# dimmerac_supervisorio_REV3.net
KiCad netlist of a schematic drawn in EAGLE
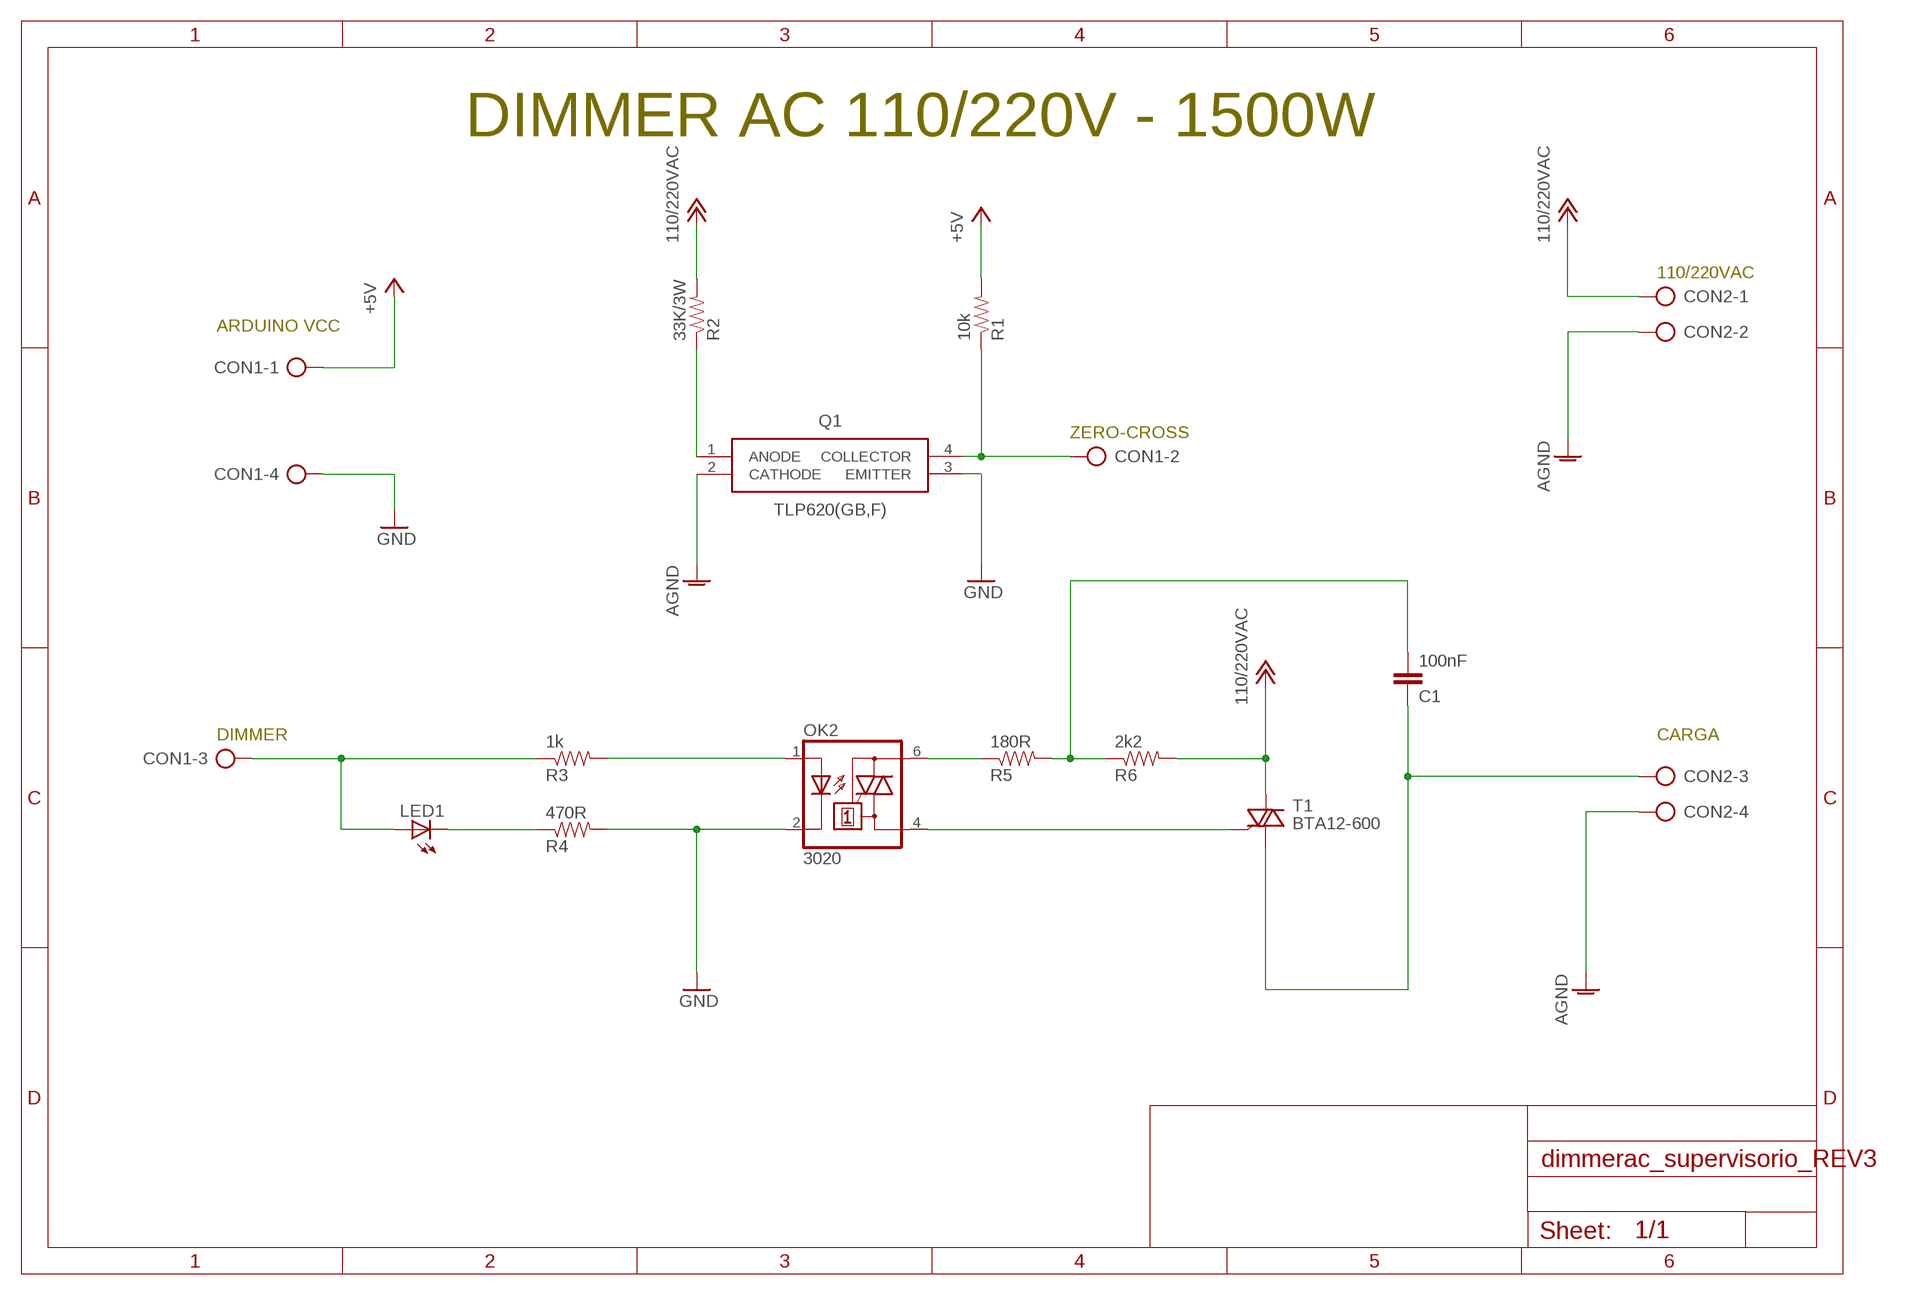
[diagram p0: schematic, sheet 1]

(export (version "E")
  (design (tool "Eeschema 10.0.6"))
  (components
    (comp (ref "C1")
      (value "100nF")
      (footprint "eagle-import:C15B7")
      (libsource (lib "eagle-import") (part "CAP_600V"))
    )
    (comp (ref "CON1")
      (value "AK500/4")
      (footprint "eagle-import:AK500_4")
      (libsource (lib "eagle-import") (part "AK500/4"))
    )
    (comp (ref "CON2")
      (value "AK500/4")
      (footprint "eagle-import:AK500_4")
      (libsource (lib "eagle-import") (part "AK500/4"))
    )
    (comp (ref "LED1")
      (value "LED5MM")
      (footprint "eagle-import:LED5MM")
      (libsource (lib "eagle-import") (part "LED5MM"))
    )
    (comp (ref "OK2")
      (value "3020")
      (footprint "eagle-import:DIL06")
      (fields (field (name "MF") "FAIRCHILD SEMICONDUCTOR") (field (name "MPN") "MOC3020-M"))
      (libsource (lib "eagle-import") (part "MOC30M20"))
    )
    (comp (ref "Q1")
      (value "TLP620(GB,F)")
      (footprint "eagle-import:DIP762W60P254L448H380Q4N")
      (fields (field (name "RS_PART_NUMBER") "0186189"))
      (libsource (lib "eagle-import") (part "TLP620(GB,F)"))
    )
    (comp (ref "R1")
      (value "10k")
      (footprint "eagle-import:AXIAL-0.3")
      (libsource (lib "eagle-import") (part "RESISTORAXIAL-0.3"))
    )
    (comp (ref "R2")
      (value "33K/3W")
      (footprint "eagle-import:AXIAL-0.6")
      (libsource (lib "eagle-import") (part "RES_5W"))
    )
    (comp (ref "R3")
      (value "1k")
      (footprint "eagle-import:AXIAL-0.3")
      (libsource (lib "eagle-import") (part "RESISTORAXIAL-0.3"))
    )
    (comp (ref "R4")
      (value "470R")
      (footprint "eagle-import:AXIAL-0.3")
      (libsource (lib "eagle-import") (part "RESISTORAXIAL-0.3"))
    )
    (comp (ref "R5")
      (value "180R")
      (footprint "eagle-import:AXIAL-0.3")
      (libsource (lib "eagle-import") (part "RESISTORAXIAL-0.3"))
    )
    (comp (ref "R6")
      (value "2k2")
      (footprint "eagle-import:AXIAL-0.3")
      (libsource (lib "eagle-import") (part "RESISTORAXIAL-0.3"))
    )
    (comp (ref "T1")
      (value "BTA12-600")
      (footprint "eagle-import:TO220BH")
      (libsource (lib "eagle-import") (part "BT138-H"))
    )
  )
  (nets
    (net (code "1") (name "+5V") (class "Default")
      (node (ref "CON1") (pin "1") (pinfunction "KL_1") (pintype "passive"))
      (node (ref "R1") (pin "P$2") (pinfunction "2_P$2") (pintype "passive"))
    )
    (net (code "2") (name "110{slash}220VAC") (class "Default")
      (node (ref "CON2") (pin "1") (pinfunction "KL_1") (pintype "passive"))
      (node (ref "R2") (pin "P$2") (pinfunction "2_P$2") (pintype "passive"))
      (node (ref "R6") (pin "P$2") (pinfunction "2_P$2") (pintype "passive"))
      (node (ref "T1") (pin "T2") (pinfunction "A2_T2") (pintype "passive"))
    )
    (net (code "3") (name "AGND") (class "Default")
      (node (ref "CON2") (pin "2") (pinfunction "KL_2") (pintype "passive"))
      (node (ref "CON2") (pin "4") (pinfunction "KL_4") (pintype "passive"))
      (node (ref "Q1") (pin "2") (pinfunction "CATHODE_2") (pintype "passive"))
    )
    (net (code "4") (name "GND") (class "Default")
      (node (ref "CON1") (pin "4") (pinfunction "KL_4") (pintype "passive"))
      (node (ref "OK2") (pin "2") (pinfunction "C_2") (pintype "passive"))
      (node (ref "Q1") (pin "3") (pinfunction "EMITTER_3") (pintype "passive"))
      (node (ref "R4") (pin "P$2") (pinfunction "2_P$2") (pintype "passive"))
    )
    (net (code "5") (name "Net-(CON1B-KL)") (class "Default")
      (node (ref "CON1") (pin "2") (pinfunction "KL_2") (pintype "passive"))
      (node (ref "Q1") (pin "4") (pinfunction "COLLECTOR_4") (pintype "passive"))
      (node (ref "R1") (pin "P$1") (pinfunction "1_P$1") (pintype "passive"))
    )
    (net (code "6") (name "Net-(CON1C-KL)") (class "Default")
      (node (ref "CON1") (pin "3") (pinfunction "KL_3") (pintype "passive"))
      (node (ref "LED1") (pin "A") (pinfunction "A_A") (pintype "passive"))
      (node (ref "R3") (pin "P$1") (pinfunction "1_P$1") (pintype "passive"))
    )
    (net (code "7") (name "Net-(CON2C-KL)") (class "Default")
      (node (ref "C1") (pin "1") (pinfunction "1_1") (pintype "passive"))
      (node (ref "CON2") (pin "3") (pinfunction "KL_3") (pintype "passive"))
      (node (ref "T1") (pin "T1") (pinfunction "A1_T1") (pintype "passive"))
    )
    (net (code "8") (name "Net-(LED1-C)") (class "Default")
      (node (ref "LED1") (pin "K") (pinfunction "C_K") (pintype "passive"))
      (node (ref "R4") (pin "P$1") (pinfunction "1_P$1") (pintype "passive"))
    )
    (net (code "9") (name "Net-(OK2-A)") (class "Default")
      (node (ref "OK2") (pin "1") (pinfunction "A_1") (pintype "passive"))
      (node (ref "R3") (pin "P$2") (pinfunction "2_P$2") (pintype "passive"))
    )
    (net (code "10") (name "Net-(OK2-A1)") (class "Default")
      (node (ref "OK2") (pin "4") (pinfunction "A1_4") (pintype "passive"))
      (node (ref "T1") (pin "G") (pinfunction "G_G") (pintype "passive"))
    )
    (net (code "11") (name "Net-(OK2-A2)") (class "Default")
      (node (ref "OK2") (pin "6") (pinfunction "A2_6") (pintype "passive"))
      (node (ref "R5") (pin "P$1") (pinfunction "1_P$1") (pintype "passive"))
    )
    (net (code "12") (name "Net-(Q1-ANODE)") (class "Default")
      (node (ref "Q1") (pin "1") (pinfunction "ANODE_1") (pintype "passive"))
      (node (ref "R2") (pin "P$1") (pinfunction "1_P$1") (pintype "passive"))
    )
    (net (code "13") (name "Net-(R5-2)") (class "Default")
      (node (ref "C1") (pin "2") (pinfunction "2_2") (pintype "passive"))
      (node (ref "R5") (pin "P$2") (pinfunction "2_P$2") (pintype "passive"))
      (node (ref "R6") (pin "P$1") (pinfunction "1_P$1") (pintype "passive"))
    )
  )
)
